# Missing_Pulse_Detector.net
KiCad netlist of a schematic drawn in EAGLE
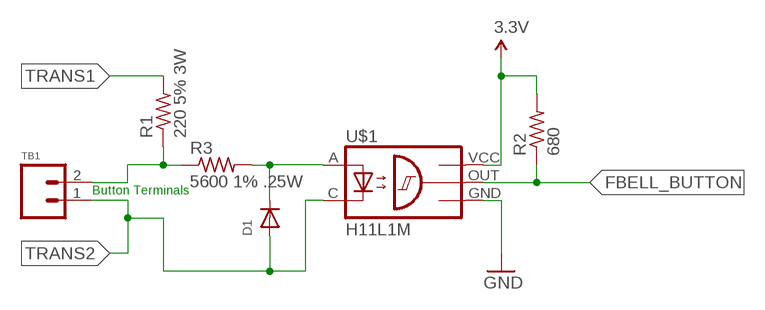
[diagram p0: schematic, sheet 1]

(export (version "E")
  (design (tool "Eeschema 10.0.6"))
  (components
    (comp (ref "D1")
      (value "DIODE0603")
      (footprint "eagle-import:0603_DIODE")
      (libsource (lib "eagle-import") (part "DIODE0603"))
    )
    (comp (ref "R1")
      (value "220 5% 3W")
      (footprint "eagle-import:4122_RESISTOR")
      (libsource (lib "eagle-import") (part "RESISTOR4122"))
    )
    (comp (ref "R2")
      (value "680")
      (footprint "eagle-import:0603_RESISTOR")
      (libsource (lib "eagle-import") (part "RESISTOR0603"))
    )
    (comp (ref "R3")
      (value "5600 1% .25W")
      (footprint "eagle-import:1206_RESISTOR")
      (libsource (lib "eagle-import") (part "RESISTOR1206"))
    )
    (comp (ref "TB1")
      (value "TERMINAL_BLOCK_2")
      (footprint "eagle-import:TERMINAL_BLOCK_2")
      (fields (field (name "MANF") "Phoenix"))
      (libsource (lib "eagle-import") (part "TERMINAL_BLOCK_2"))
    )
    (comp (ref "U$1")
      (value "H11L1M")
      (footprint "eagle-import:SOIC6")
      (fields (field (name "MANF") "Fairchild Semiconductor"))
      (libsource (lib "eagle-import") (part "H11L1M"))
    )
  )
  (nets
    (net (code "1") (name "3.3V") (class "Default")
      (node (ref "R2") (pin "2") (pinfunction "2_2") (pintype "passive"))
      (node (ref "U$1") (pin "VCC") (pinfunction "VCC_VCC") (pintype "passive"))
    )
    (net (code "2") (name "FBELL_BUTTON") (class "Default")
      (node (ref "R2") (pin "1") (pinfunction "1_1") (pintype "passive"))
      (node (ref "U$1") (pin "OUT") (pinfunction "OUT_OUT") (pintype "passive"))
    )
    (net (code "3") (name "GND") (class "Default")
      (node (ref "U$1") (pin "GND") (pinfunction "GND_GND") (pintype "passive"))
    )
    (net (code "4") (name "Net-(D1-PadC)") (class "Default")
      (node (ref "D1") (pin "C") (pinfunction "C_C") (pintype "passive"))
      (node (ref "R3") (pin "2") (pinfunction "2_2") (pintype "passive"))
      (node (ref "U$1") (pin "A") (pinfunction "A_A") (pintype "passive"))
    )
    (net (code "5") (name "Net-(R1-Pad1)") (class "Default")
      (node (ref "R1") (pin "1") (pinfunction "1_1") (pintype "passive"))
      (node (ref "R3") (pin "1") (pinfunction "1_1") (pintype "passive"))
      (node (ref "TB1") (pin "2") (pinfunction "2_2") (pintype "passive"))
    )
    (net (code "6") (name "TRANS1") (class "Default")
      (node (ref "R1") (pin "2") (pinfunction "2_2") (pintype "passive"))
    )
    (net (code "7") (name "TRANS2") (class "Default")
      (node (ref "D1") (pin "A") (pinfunction "A_A") (pintype "passive"))
      (node (ref "TB1") (pin "1") (pinfunction "1_1") (pintype "passive"))
      (node (ref "U$1") (pin "C") (pinfunction "C_C") (pintype "passive"))
    )
  )
)
